# Blupill_SCSI_a.net
KiCad netlist of a schematic drawn in EAGLE
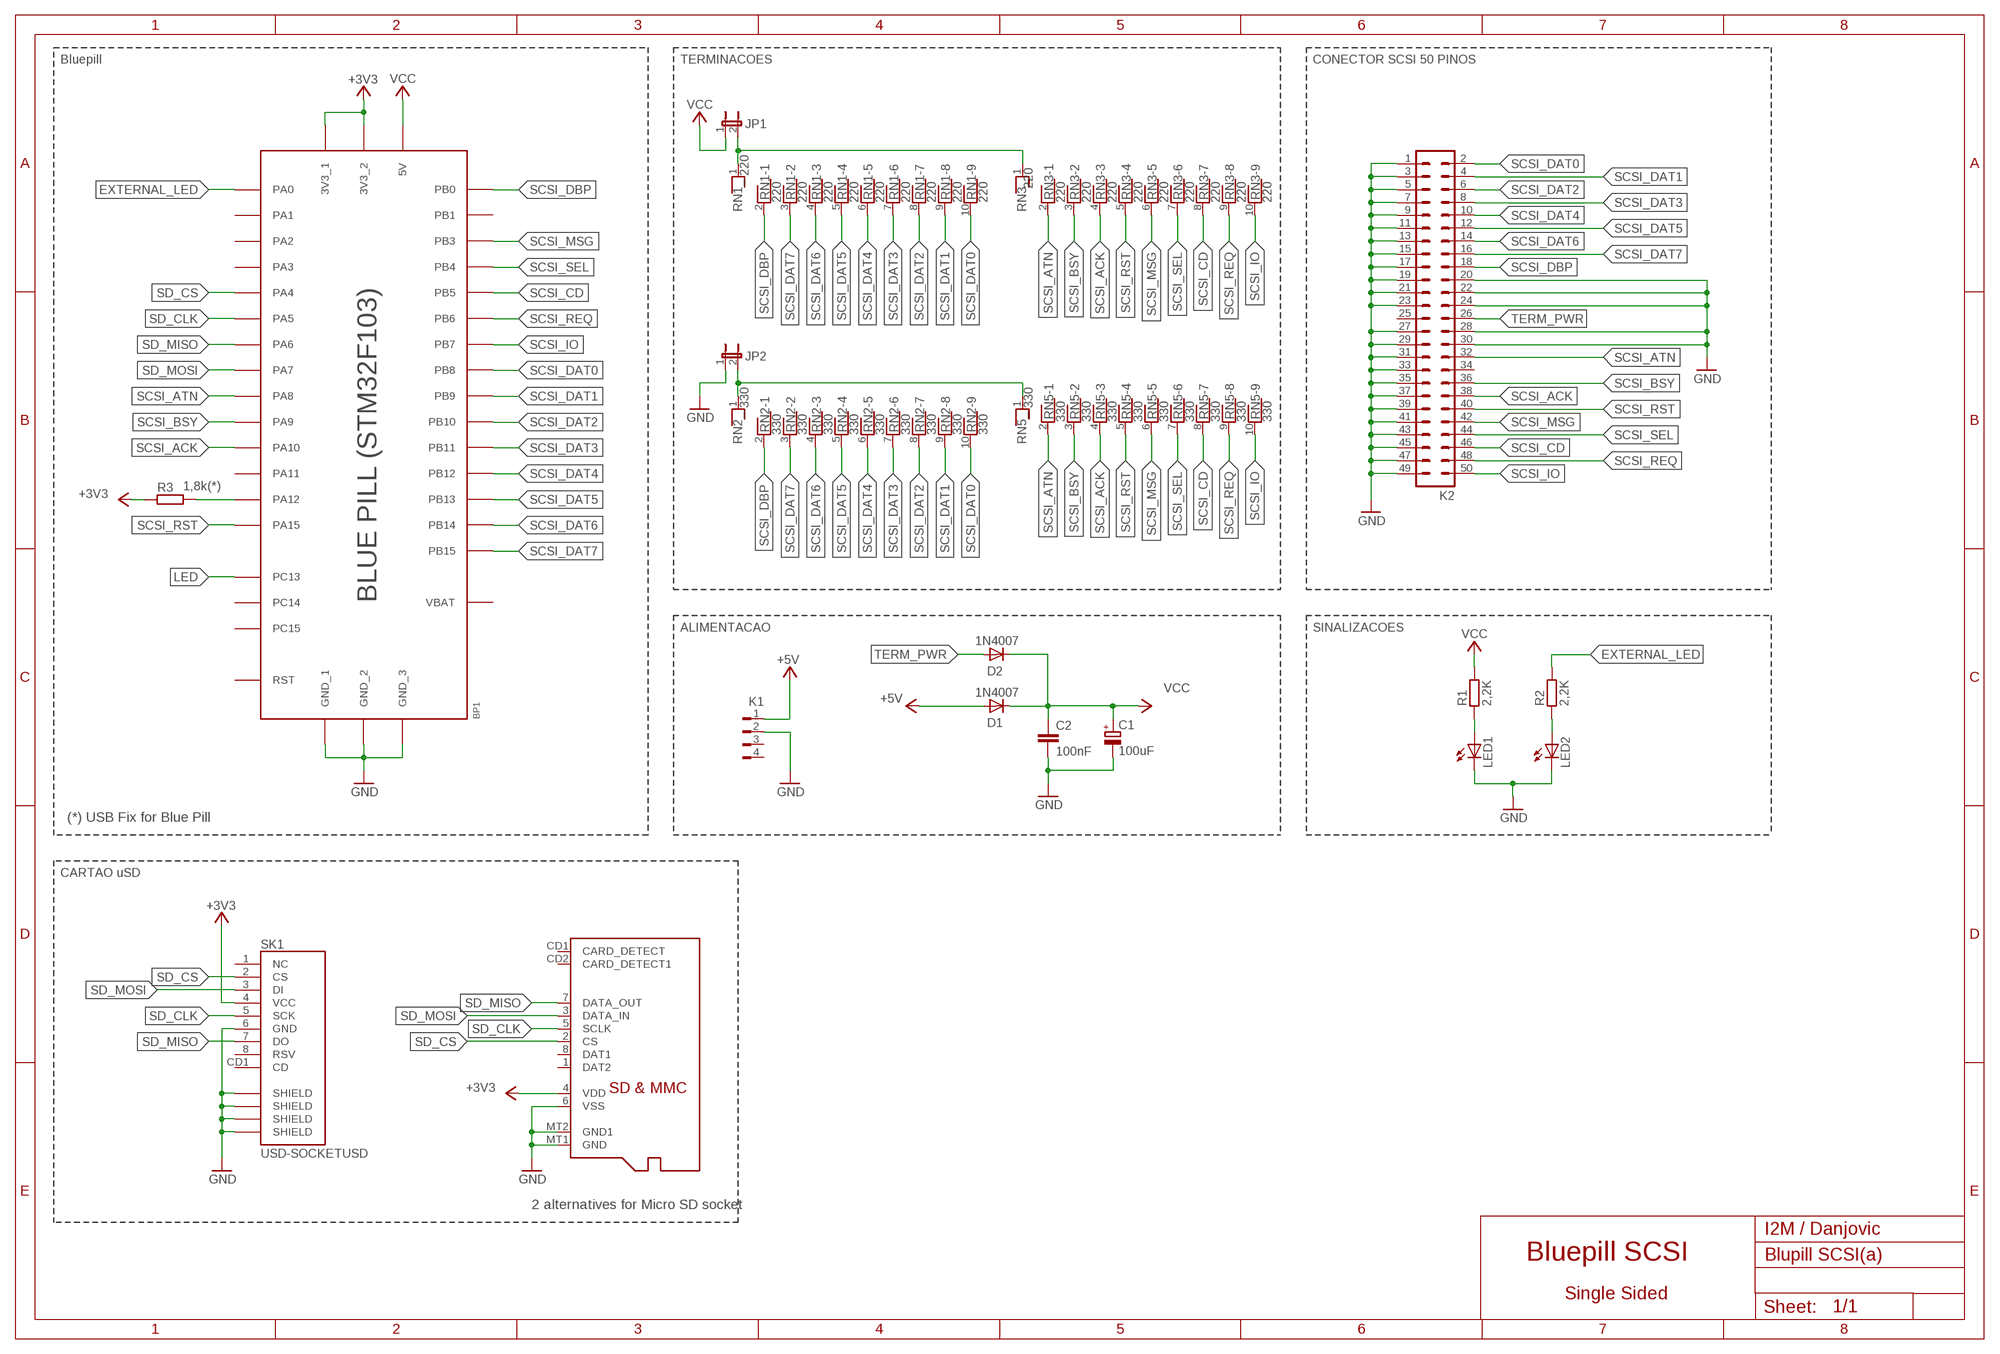
[diagram p0: schematic, sheet 1]

(export (version "E")
  (design (tool "Eeschema 10.0.6"))
  (components
    (comp (ref "BP1")
      (value "BLUE_PILL")
      (footprint "eagle-import:BLUE_PILL")
      (libsource (lib "eagle-import") (part "BLUE_PILL"))
    )
    (comp (ref "C1")
      (value "100uF")
      (footprint "eagle-import:E2,5-7")
      (libsource (lib "eagle-import") (part "CPOL-EUE2.5-7"))
    )
    (comp (ref "C2")
      (value "100nF")
      (footprint "eagle-import:C050-025X075")
      (libsource (lib "eagle-import") (part "C-EU050-025X075"))
    )
    (comp (ref "D1")
      (value "1N4007")
      (footprint "eagle-import:DO41-10")
      (libsource (lib "eagle-import") (part "1N4004"))
    )
    (comp (ref "D2")
      (value "1N4007")
      (footprint "eagle-import:DO41-10")
      (libsource (lib "eagle-import") (part "1N4004"))
    )
    (comp (ref "JP1")
      (value "JP1E")
      (footprint "eagle-import:JP1")
      (libsource (lib "eagle-import") (part "JP1E"))
    )
    (comp (ref "JP2")
      (value "JP1E")
      (footprint "eagle-import:JP1")
      (libsource (lib "eagle-import") (part "JP1E"))
    )
    (comp (ref "K1")
      (value "FLOP-4W")
      (footprint "eagle-import:FLOP-4V")
      (libsource (lib "eagle-import") (part "FLOP-4W"))
    )
    (comp (ref "K2")
      (value "ML50L")
      (footprint "eagle-import:ML50L")
      (libsource (lib "eagle-import") (part "ML50L"))
    )
    (comp (ref "LED1")
      (value "LED3MM")
      (footprint "eagle-import:LED3MM")
      (libsource (lib "eagle-import") (part "LED3MM"))
    )
    (comp (ref "LED2")
      (value "LED3MM")
      (footprint "eagle-import:LED3MM")
      (libsource (lib "eagle-import") (part "LED3MM"))
    )
    (comp (ref "R1")
      (value "2,2K")
      (footprint "eagle-import:0207_10")
      (libsource (lib "eagle-import") (part "R-EU_0207/10"))
    )
    (comp (ref "R2")
      (value "2,2K")
      (footprint "eagle-import:0207_10")
      (libsource (lib "eagle-import") (part "R-EU_0207/10"))
    )
    (comp (ref "R3")
      (value "1,8k(*)")
      (footprint "eagle-import:0207_10")
      (libsource (lib "eagle-import") (part "R-EU_0207/10"))
    )
    (comp (ref "RN1")
      (value "220")
      (footprint "eagle-import:RN-10")
      (libsource (lib "eagle-import") (part "RNX9"))
    )
    (comp (ref "RN2")
      (value "330")
      (footprint "eagle-import:RN-10")
      (libsource (lib "eagle-import") (part "RNX9"))
    )
    (comp (ref "RN3")
      (value "220")
      (footprint "eagle-import:RN-10")
      (libsource (lib "eagle-import") (part "RNX9"))
    )
    (comp (ref "RN5")
      (value "330")
      (footprint "eagle-import:RN-10")
      (libsource (lib "eagle-import") (part "RNX9"))
    )
    (comp (ref "SK1")
      (value "USD-SOCKETUSD")
      (footprint "eagle-import:USD-SOCKET-PP")
      (libsource (lib "eagle-import") (part "USD-SOCKETUSD"))
    )
    (comp (ref "U$2")
      (value "MICROSD")
      (footprint "eagle-import:MICROSD")
      (libsource (lib "eagle-import") (part "MICROSD"))
    )
  )
  (nets
    (net (code "1") (name "+3V3") (class "Default")
      (node (ref "BP1") (pin "3,3V_1") (pinfunction "3V3_1_3,3V_1") (pintype "power_in"))
      (node (ref "BP1") (pin "3,3V_2") (pinfunction "3V3_2_3,3V_2") (pintype "power_in"))
      (node (ref "R3") (pin "1") (pinfunction "1_1") (pintype "passive"))
      (node (ref "SK1") (pin "4") (pinfunction "VCC_4") (pintype "bidirectional"))
      (node (ref "U$2") (pin "4") (pinfunction "VDD_4") (pintype "power_in"))
    )
    (net (code "2") (name "+5V") (class "Default")
      (node (ref "D1") (pin "A") (pinfunction "A_A") (pintype "passive"))
      (node (ref "K1") (pin "1") (pinfunction "1_1") (pintype "passive"))
    )
    (net (code "3") (name "/VBAT") (class "Default")
      (node (ref "BP1") (pin "VB") (pinfunction "VBAT_VB") (pintype "power_in"))
    )
    (net (code "4") (name "EXTERNAL_LED") (class "Default")
      (node (ref "BP1") (pin "A0") (pinfunction "PA0_A0") (pintype "bidirectional"))
      (node (ref "R2") (pin "2") (pinfunction "2_2") (pintype "passive"))
    )
    (net (code "5") (name "GND") (class "Default")
      (node (ref "BP1") (pin "GND1") (pinfunction "GND_1_GND1") (pintype "power_in"))
      (node (ref "BP1") (pin "GND2") (pinfunction "GND_2_GND2") (pintype "power_in"))
      (node (ref "BP1") (pin "GND3") (pinfunction "GND_3_GND3") (pintype "power_in"))
      (node (ref "C1") (pin "-") (pinfunction "-_-") (pintype "passive"))
      (node (ref "C2") (pin "2") (pinfunction "2_2") (pintype "passive"))
      (node (ref "JP2") (pin "1") (pinfunction "1_1") (pintype "passive"))
      (node (ref "K1") (pin "2") (pinfunction "2_2") (pintype "passive"))
      (node (ref "K2") (pin "1") (pinfunction "1_1") (pintype "passive"))
      (node (ref "K2") (pin "11") (pinfunction "11_11") (pintype "passive"))
      (node (ref "K2") (pin "13") (pinfunction "13_13") (pintype "passive"))
      (node (ref "K2") (pin "15") (pinfunction "15_15") (pintype "passive"))
      (node (ref "K2") (pin "17") (pinfunction "17_17") (pintype "passive"))
      (node (ref "K2") (pin "19") (pinfunction "19_19") (pintype "passive"))
      (node (ref "K2") (pin "20") (pinfunction "20_20") (pintype "passive"))
      (node (ref "K2") (pin "21") (pinfunction "21_21") (pintype "passive"))
      (node (ref "K2") (pin "22") (pinfunction "22_22") (pintype "passive"))
      (node (ref "K2") (pin "23") (pinfunction "23_23") (pintype "passive"))
      (node (ref "K2") (pin "24") (pinfunction "24_24") (pintype "passive"))
      (node (ref "K2") (pin "27") (pinfunction "27_27") (pintype "passive"))
      (node (ref "K2") (pin "28") (pinfunction "28_28") (pintype "passive"))
      (node (ref "K2") (pin "29") (pinfunction "29_29") (pintype "passive"))
      (node (ref "K2") (pin "3") (pinfunction "3_3") (pintype "passive"))
      (node (ref "K2") (pin "30") (pinfunction "30_30") (pintype "passive"))
      (node (ref "K2") (pin "31") (pinfunction "31_31") (pintype "passive"))
      (node (ref "K2") (pin "33") (pinfunction "33_33") (pintype "passive"))
      (node (ref "K2") (pin "35") (pinfunction "35_35") (pintype "passive"))
      (node (ref "K2") (pin "37") (pinfunction "37_37") (pintype "passive"))
      (node (ref "K2") (pin "39") (pinfunction "39_39") (pintype "passive"))
      (node (ref "K2") (pin "41") (pinfunction "41_41") (pintype "passive"))
      (node (ref "K2") (pin "43") (pinfunction "43_43") (pintype "passive"))
      (node (ref "K2") (pin "45") (pinfunction "45_45") (pintype "passive"))
      (node (ref "K2") (pin "47") (pinfunction "47_47") (pintype "passive"))
      (node (ref "K2") (pin "49") (pinfunction "49_49") (pintype "passive"))
      (node (ref "K2") (pin "5") (pinfunction "5_5") (pintype "passive"))
      (node (ref "K2") (pin "7") (pinfunction "7_7") (pintype "passive"))
      (node (ref "K2") (pin "9") (pinfunction "9_9") (pintype "passive"))
      (node (ref "LED1") (pin "K") (pinfunction "C_K") (pintype "passive"))
      (node (ref "LED2") (pin "K") (pinfunction "C_K") (pintype "passive"))
      (node (ref "SK1") (pin "6") (pinfunction "GND_6") (pintype "bidirectional"))
      (node (ref "SK1") (pin "GND1") (pinfunction "SHIELD_GND1") (pintype "power_in"))
      (node (ref "SK1") (pin "GND2") (pinfunction "SHIELD_GND2") (pintype "power_in"))
      (node (ref "SK1") (pin "GND3") (pinfunction "SHIELD_GND3") (pintype "power_in"))
      (node (ref "SK1") (pin "GND4") (pinfunction "SHIELD_GND4") (pintype "power_in"))
      (node (ref "U$2") (pin "6") (pinfunction "VSS_6") (pintype "power_in"))
      (node (ref "U$2") (pin "MT1") (pinfunction "GND_MT1") (pintype "power_in"))
      (node (ref "U$2") (pin "MT2") (pinfunction "GND1_MT2") (pintype "power_in"))
    )
    (net (code "6") (name "LED") (class "Default")
      (node (ref "BP1") (pin "C13") (pinfunction "PC13_C13") (pintype "bidirectional"))
    )
    (net (code "7") (name "Net-(BP1-PA12)") (class "Default")
      (node (ref "BP1") (pin "A12") (pinfunction "PA12_A12") (pintype "bidirectional"))
      (node (ref "R3") (pin "2") (pinfunction "2_2") (pintype "passive"))
    )
    (net (code "8") (name "Net-(JP1-Pad2)") (class "Default")
      (node (ref "JP1") (pin "2") (pinfunction "2_2") (pintype "passive"))
      (node (ref "RN1") (pin "1") (pinfunction "1_1") (pintype "passive"))
      (node (ref "RN3") (pin "1") (pinfunction "1_1") (pintype "passive"))
    )
    (net (code "9") (name "Net-(JP2-Pad2)") (class "Default")
      (node (ref "JP2") (pin "2") (pinfunction "2_2") (pintype "passive"))
      (node (ref "RN2") (pin "1") (pinfunction "1_1") (pintype "passive"))
      (node (ref "RN5") (pin "1") (pinfunction "1_1") (pintype "passive"))
    )
    (net (code "10") (name "Net-(LED1-PadA)") (class "Default")
      (node (ref "LED1") (pin "A") (pinfunction "A_A") (pintype "passive"))
      (node (ref "R1") (pin "1") (pinfunction "1_1") (pintype "passive"))
    )
    (net (code "11") (name "Net-(LED2-PadA)") (class "Default")
      (node (ref "LED2") (pin "A") (pinfunction "A_A") (pintype "passive"))
      (node (ref "R2") (pin "1") (pinfunction "1_1") (pintype "passive"))
    )
    (net (code "12") (name "SCSI_ACK") (class "Default")
      (node (ref "BP1") (pin "A10") (pinfunction "PA10_A10") (pintype "bidirectional"))
      (node (ref "K2") (pin "38") (pinfunction "38_38") (pintype "passive"))
      (node (ref "RN3") (pin "4") (pinfunction "1_4") (pintype "passive"))
      (node (ref "RN5") (pin "4") (pinfunction "1_4") (pintype "passive"))
    )
    (net (code "13") (name "SCSI_ATN") (class "Default")
      (node (ref "BP1") (pin "A8") (pinfunction "PA8_A8") (pintype "bidirectional"))
      (node (ref "K2") (pin "32") (pinfunction "32_32") (pintype "passive"))
      (node (ref "RN3") (pin "2") (pinfunction "1_2") (pintype "passive"))
      (node (ref "RN5") (pin "2") (pinfunction "1_2") (pintype "passive"))
    )
    (net (code "14") (name "SCSI_BSY") (class "Default")
      (node (ref "BP1") (pin "A9") (pinfunction "PA9_A9") (pintype "bidirectional"))
      (node (ref "K2") (pin "36") (pinfunction "36_36") (pintype "passive"))
      (node (ref "RN3") (pin "3") (pinfunction "1_3") (pintype "passive"))
      (node (ref "RN5") (pin "3") (pinfunction "1_3") (pintype "passive"))
    )
    (net (code "15") (name "SCSI_CD") (class "Default")
      (node (ref "BP1") (pin "B5") (pinfunction "PB5_B5") (pintype "bidirectional"))
      (node (ref "K2") (pin "46") (pinfunction "46_46") (pintype "passive"))
      (node (ref "RN3") (pin "8") (pinfunction "1_8") (pintype "passive"))
      (node (ref "RN5") (pin "8") (pinfunction "1_8") (pintype "passive"))
    )
    (net (code "16") (name "SCSI_DAT0") (class "Default")
      (node (ref "BP1") (pin "B8") (pinfunction "PB8_B8") (pintype "bidirectional"))
      (node (ref "K2") (pin "2") (pinfunction "2_2") (pintype "passive"))
      (node (ref "RN1") (pin "10") (pinfunction "1_10") (pintype "passive"))
      (node (ref "RN2") (pin "10") (pinfunction "1_10") (pintype "passive"))
    )
    (net (code "17") (name "SCSI_DAT1") (class "Default")
      (node (ref "BP1") (pin "B9") (pinfunction "PB9_B9") (pintype "bidirectional"))
      (node (ref "K2") (pin "4") (pinfunction "4_4") (pintype "passive"))
      (node (ref "RN1") (pin "9") (pinfunction "1_9") (pintype "passive"))
      (node (ref "RN2") (pin "9") (pinfunction "1_9") (pintype "passive"))
    )
    (net (code "18") (name "SCSI_DAT2") (class "Default")
      (node (ref "BP1") (pin "B10") (pinfunction "PB10_B10") (pintype "bidirectional"))
      (node (ref "K2") (pin "6") (pinfunction "6_6") (pintype "passive"))
      (node (ref "RN1") (pin "8") (pinfunction "1_8") (pintype "passive"))
      (node (ref "RN2") (pin "8") (pinfunction "1_8") (pintype "passive"))
    )
    (net (code "19") (name "SCSI_DAT3") (class "Default")
      (node (ref "BP1") (pin "B11") (pinfunction "PB11_B11") (pintype "bidirectional"))
      (node (ref "K2") (pin "8") (pinfunction "8_8") (pintype "passive"))
      (node (ref "RN1") (pin "7") (pinfunction "1_7") (pintype "passive"))
      (node (ref "RN2") (pin "7") (pinfunction "1_7") (pintype "passive"))
    )
    (net (code "20") (name "SCSI_DAT4") (class "Default")
      (node (ref "BP1") (pin "B12") (pinfunction "PB12_B12") (pintype "bidirectional"))
      (node (ref "K2") (pin "10") (pinfunction "10_10") (pintype "passive"))
      (node (ref "RN1") (pin "6") (pinfunction "1_6") (pintype "passive"))
      (node (ref "RN2") (pin "6") (pinfunction "1_6") (pintype "passive"))
    )
    (net (code "21") (name "SCSI_DAT5") (class "Default")
      (node (ref "BP1") (pin "B13") (pinfunction "PB13_B13") (pintype "bidirectional"))
      (node (ref "K2") (pin "12") (pinfunction "12_12") (pintype "passive"))
      (node (ref "RN1") (pin "5") (pinfunction "1_5") (pintype "passive"))
      (node (ref "RN2") (pin "5") (pinfunction "1_5") (pintype "passive"))
    )
    (net (code "22") (name "SCSI_DAT6") (class "Default")
      (node (ref "BP1") (pin "B14") (pinfunction "PB14_B14") (pintype "bidirectional"))
      (node (ref "K2") (pin "14") (pinfunction "14_14") (pintype "passive"))
      (node (ref "RN1") (pin "4") (pinfunction "1_4") (pintype "passive"))
      (node (ref "RN2") (pin "4") (pinfunction "1_4") (pintype "passive"))
    )
    (net (code "23") (name "SCSI_DAT7") (class "Default")
      (node (ref "BP1") (pin "B15") (pinfunction "PB15_B15") (pintype "bidirectional"))
      (node (ref "K2") (pin "16") (pinfunction "16_16") (pintype "passive"))
      (node (ref "RN1") (pin "3") (pinfunction "1_3") (pintype "passive"))
      (node (ref "RN2") (pin "3") (pinfunction "1_3") (pintype "passive"))
    )
    (net (code "24") (name "SCSI_DBP") (class "Default")
      (node (ref "BP1") (pin "B0") (pinfunction "PB0_B0") (pintype "bidirectional"))
      (node (ref "K2") (pin "18") (pinfunction "18_18") (pintype "passive"))
      (node (ref "RN1") (pin "2") (pinfunction "1_2") (pintype "passive"))
      (node (ref "RN2") (pin "2") (pinfunction "1_2") (pintype "passive"))
    )
    (net (code "25") (name "SCSI_IO") (class "Default")
      (node (ref "BP1") (pin "B7") (pinfunction "PB7_B7") (pintype "bidirectional"))
      (node (ref "K2") (pin "50") (pinfunction "50_50") (pintype "passive"))
      (node (ref "RN3") (pin "10") (pinfunction "1_10") (pintype "passive"))
      (node (ref "RN5") (pin "10") (pinfunction "1_10") (pintype "passive"))
    )
    (net (code "26") (name "SCSI_MSG") (class "Default")
      (node (ref "BP1") (pin "B3") (pinfunction "PB3_B3") (pintype "bidirectional"))
      (node (ref "K2") (pin "42") (pinfunction "42_42") (pintype "passive"))
      (node (ref "RN3") (pin "6") (pinfunction "1_6") (pintype "passive"))
      (node (ref "RN5") (pin "6") (pinfunction "1_6") (pintype "passive"))
    )
    (net (code "27") (name "SCSI_REQ") (class "Default")
      (node (ref "BP1") (pin "B6") (pinfunction "PB6_B6") (pintype "bidirectional"))
      (node (ref "K2") (pin "48") (pinfunction "48_48") (pintype "passive"))
      (node (ref "RN3") (pin "9") (pinfunction "1_9") (pintype "passive"))
      (node (ref "RN5") (pin "9") (pinfunction "1_9") (pintype "passive"))
    )
    (net (code "28") (name "SCSI_RST") (class "Default")
      (node (ref "BP1") (pin "A15") (pinfunction "PA15_A15") (pintype "bidirectional"))
      (node (ref "K2") (pin "40") (pinfunction "40_40") (pintype "passive"))
      (node (ref "RN3") (pin "5") (pinfunction "1_5") (pintype "passive"))
      (node (ref "RN5") (pin "5") (pinfunction "1_5") (pintype "passive"))
    )
    (net (code "29") (name "SCSI_SEL") (class "Default")
      (node (ref "BP1") (pin "B4") (pinfunction "PB4_B4") (pintype "bidirectional"))
      (node (ref "K2") (pin "44") (pinfunction "44_44") (pintype "passive"))
      (node (ref "RN3") (pin "7") (pinfunction "1_7") (pintype "passive"))
      (node (ref "RN5") (pin "7") (pinfunction "1_7") (pintype "passive"))
    )
    (net (code "30") (name "SD_CLK") (class "Default")
      (node (ref "BP1") (pin "A5") (pinfunction "PA5_A5") (pintype "bidirectional"))
      (node (ref "SK1") (pin "5") (pinfunction "SCK_5") (pintype "bidirectional"))
      (node (ref "U$2") (pin "5") (pinfunction "SCLK_5") (pintype "input"))
    )
    (net (code "31") (name "SD_CS") (class "Default")
      (node (ref "BP1") (pin "A4") (pinfunction "PA4_A4") (pintype "bidirectional"))
      (node (ref "SK1") (pin "2") (pinfunction "CS_2") (pintype "bidirectional"))
      (node (ref "U$2") (pin "2") (pinfunction "CS_2") (pintype "input"))
    )
    (net (code "32") (name "SD_MISO") (class "Default")
      (node (ref "BP1") (pin "A6") (pinfunction "PA6_A6") (pintype "bidirectional"))
      (node (ref "SK1") (pin "7") (pinfunction "DO_7") (pintype "bidirectional"))
      (node (ref "U$2") (pin "7") (pinfunction "DATA_OUT_7") (pintype "output"))
    )
    (net (code "33") (name "SD_MOSI") (class "Default")
      (node (ref "BP1") (pin "A7") (pinfunction "PA7_A7") (pintype "bidirectional"))
      (node (ref "SK1") (pin "3") (pinfunction "DI_3") (pintype "bidirectional"))
      (node (ref "U$2") (pin "3") (pinfunction "DATA_IN_3") (pintype "input"))
    )
    (net (code "34") (name "TERM_PWR") (class "Default")
      (node (ref "D2") (pin "A") (pinfunction "A_A") (pintype "passive"))
      (node (ref "K2") (pin "26") (pinfunction "26_26") (pintype "passive"))
    )
    (net (code "35") (name "VCC") (class "Default")
      (node (ref "BP1") (pin "5V") (pinfunction "5V_5V") (pintype "power_in"))
      (node (ref "C1") (pin "+") (pinfunction "+_+") (pintype "passive"))
      (node (ref "C2") (pin "1") (pinfunction "1_1") (pintype "passive"))
      (node (ref "D1") (pin "C") (pinfunction "C_C") (pintype "passive"))
      (node (ref "D2") (pin "C") (pinfunction "C_C") (pintype "passive"))
      (node (ref "JP1") (pin "1") (pinfunction "1_1") (pintype "passive"))
      (node (ref "R1") (pin "2") (pinfunction "2_2") (pintype "passive"))
    )
    (net (code "36") (name "unconnected-(BP1-PA1-PadA1)") (class "Default")
      (node (ref "BP1") (pin "A1") (pinfunction "PA1_A1") (pintype "bidirectional"))
    )
    (net (code "37") (name "unconnected-(BP1-PA2-PadA2)") (class "Default")
      (node (ref "BP1") (pin "A2") (pinfunction "PA2_A2") (pintype "bidirectional"))
    )
    (net (code "38") (name "unconnected-(BP1-PA3-PadA3)") (class "Default")
      (node (ref "BP1") (pin "A3") (pinfunction "PA3_A3") (pintype "bidirectional"))
    )
    (net (code "39") (name "unconnected-(BP1-PA11-PadA11)") (class "Default")
      (node (ref "BP1") (pin "A11") (pinfunction "PA11_A11") (pintype "bidirectional"))
    )
    (net (code "40") (name "unconnected-(BP1-PB1-PadB1)") (class "Default")
      (node (ref "BP1") (pin "B1") (pinfunction "PB1_B1") (pintype "bidirectional"))
    )
    (net (code "41") (name "unconnected-(BP1-PC14-PadC14)") (class "Default")
      (node (ref "BP1") (pin "C14") (pinfunction "PC14_C14") (pintype "bidirectional"))
    )
    (net (code "42") (name "unconnected-(BP1-PC15-PadC15)") (class "Default")
      (node (ref "BP1") (pin "C15") (pinfunction "PC15_C15") (pintype "bidirectional"))
    )
    (net (code "43") (name "unconnected-(BP1-PadRST)") (class "Default")
      (node (ref "BP1") (pin "RST") (pinfunction "RST_RST") (pintype "input"))
    )
    (net (code "44") (name "unconnected-(K1-Pad3)") (class "Default")
      (node (ref "K1") (pin "3") (pinfunction "3_3") (pintype "passive"))
    )
    (net (code "45") (name "unconnected-(K1-Pad4)") (class "Default")
      (node (ref "K1") (pin "4") (pinfunction "4_4") (pintype "passive"))
    )
    (net (code "46") (name "unconnected-(K2-Pad25)") (class "Default")
      (node (ref "K2") (pin "25") (pinfunction "25_25") (pintype "passive"))
    )
    (net (code "47") (name "unconnected-(K2-Pad34)") (class "Default")
      (node (ref "K2") (pin "34") (pinfunction "34_34") (pintype "passive"))
    )
    (net (code "48") (name "unconnected-(SK1-CD-PadCD1)") (class "Default")
      (node (ref "SK1") (pin "CD1") (pinfunction "CD_CD1") (pintype "bidirectional"))
    )
    (net (code "49") (name "unconnected-(SK1-NC-Pad1)") (class "Default")
      (node (ref "SK1") (pin "1") (pinfunction "NC_1") (pintype "bidirectional"))
    )
    (net (code "50") (name "unconnected-(SK1-RSV-Pad8)") (class "Default")
      (node (ref "SK1") (pin "8") (pinfunction "RSV_8") (pintype "bidirectional"))
    )
    (net (code "51") (name "unconnected-(U$2-CARD_DETECT-PadCD1)") (class "Default")
      (node (ref "U$2") (pin "CD1") (pinfunction "CARD_DETECT_CD1") (pintype "passive"))
    )
    (net (code "52") (name "unconnected-(U$2-CARD_DETECT1-PadCD2)") (class "Default")
      (node (ref "U$2") (pin "CD2") (pinfunction "CARD_DETECT1_CD2") (pintype "passive"))
    )
    (net (code "53") (name "unconnected-(U$2-DAT1-Pad8)") (class "Default")
      (node (ref "U$2") (pin "8") (pinfunction "DAT1_8") (pintype "bidirectional"))
    )
    (net (code "54") (name "unconnected-(U$2-DAT2-Pad1)") (class "Default")
      (node (ref "U$2") (pin "1") (pinfunction "DAT2_1") (pintype "bidirectional"))
    )
  )
)
